# AT88SC12816C.net
KiCad netlist of a schematic drawn in EAGLE
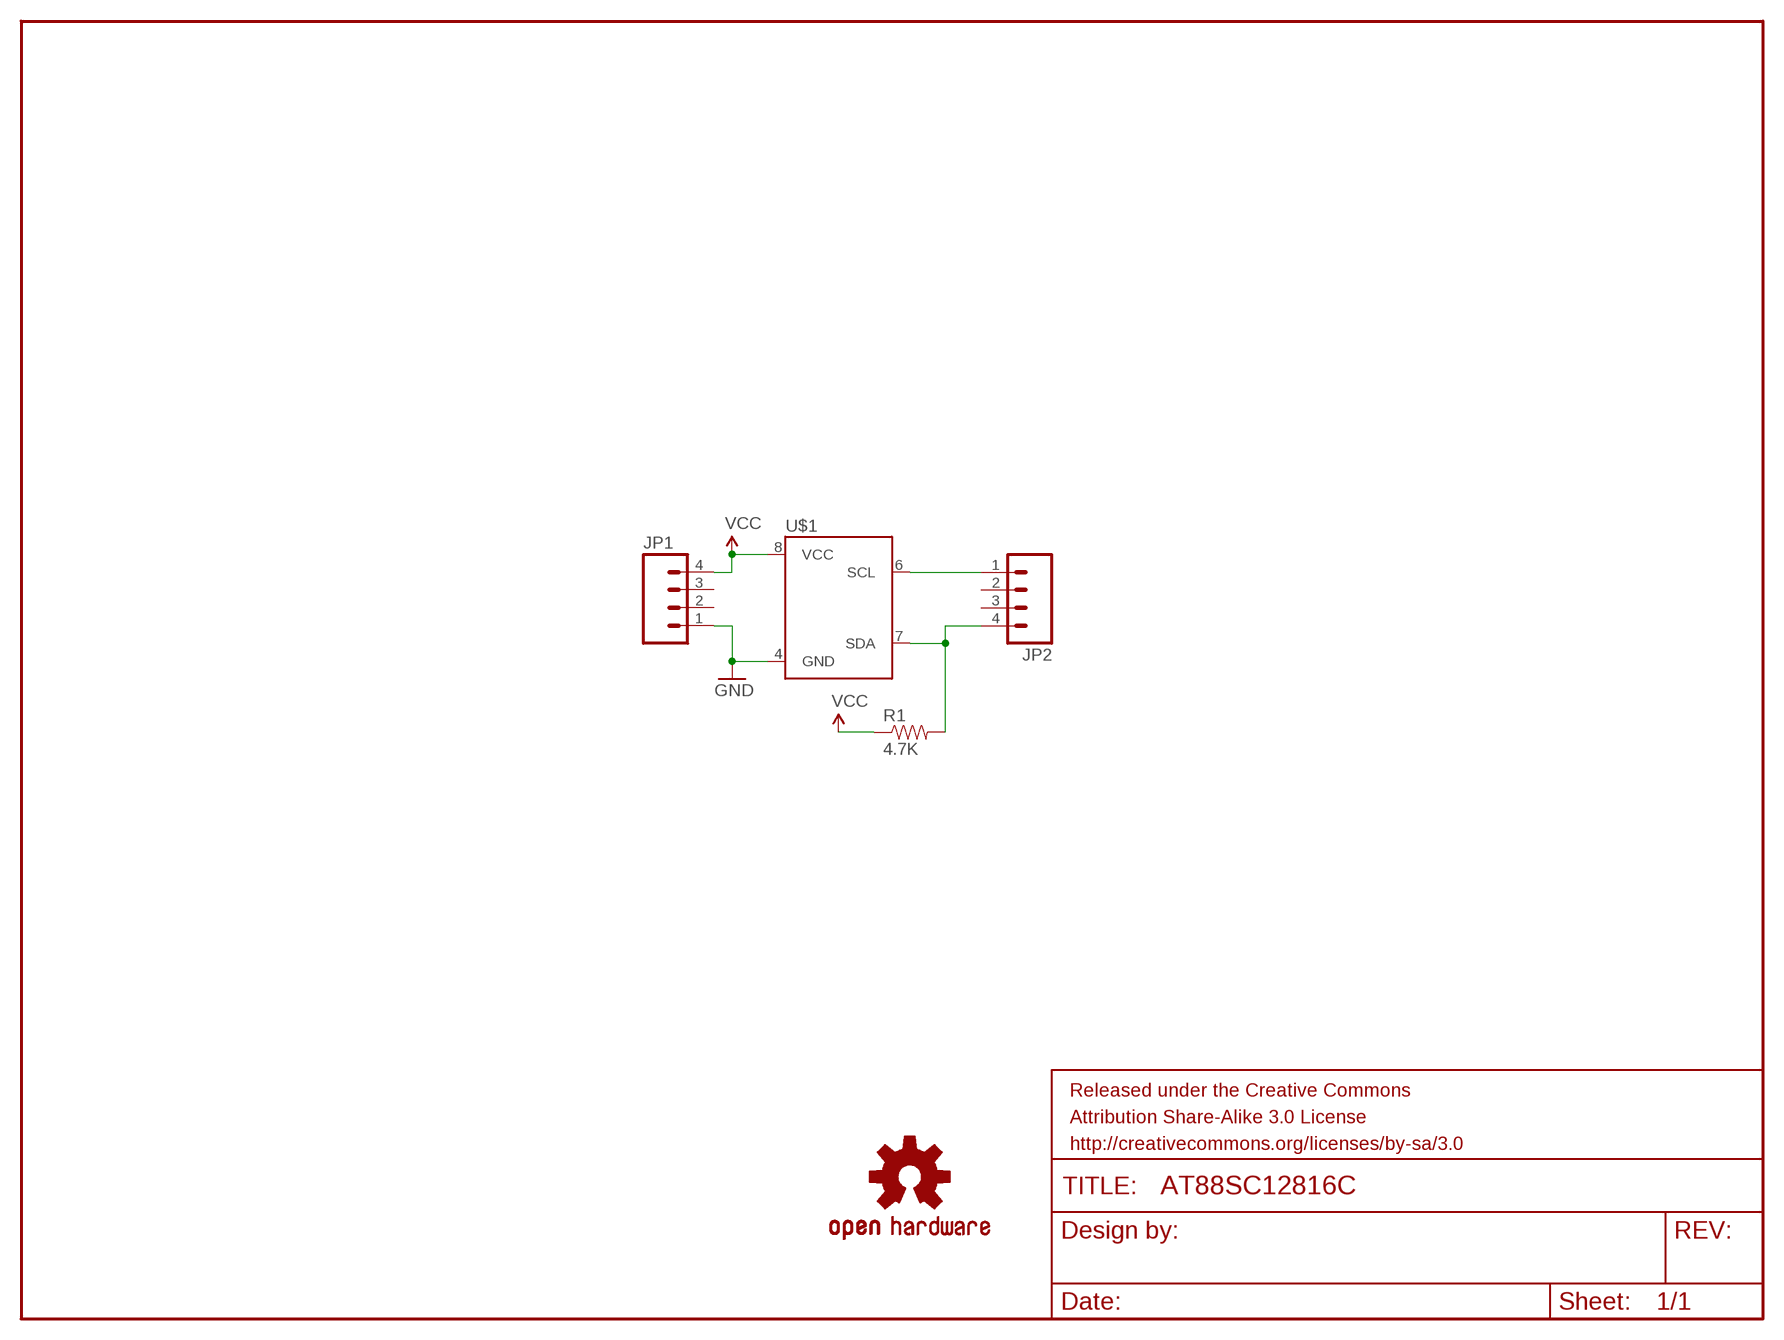
[diagram p0: schematic, sheet 1]

(export (version "E")
  (design (tool "Eeschema 10.0.6"))
  (components
    (comp (ref "FRAME1")
      (value "FRAME-LETTER")
      (footprint "eagle-import:CREATIVE_COMMONS")
      (libsource (lib "eagle-import") (part "FRAME-LETTER"))
    )
    (comp (ref "JP1")
      (value "M04LOCK")
      (footprint "eagle-import:1X04_LOCK")
      (libsource (lib "eagle-import") (part "M04LOCK"))
    )
    (comp (ref "JP2")
      (value "M04LOCK")
      (footprint "eagle-import:1X04_LOCK")
      (libsource (lib "eagle-import") (part "M04LOCK"))
    )
    (comp (ref "LOGO1")
      (value "OSHW-LOGOM")
      (footprint "eagle-import:OSHW-LOGO-M")
      (libsource (lib "eagle-import") (part "OSHW-LOGOM"))
    )
    (comp (ref "R1")
      (value "4.7K")
      (footprint "eagle-import:AXIAL-0.4")
      (libsource (lib "eagle-import") (part "RESISTORPTH-1/4W"))
    )
    (comp (ref "U$1")
      (value "AT88SCAT88SC-PDIP")
      (footprint "eagle-import:DIL08")
      (libsource (lib "eagle-import") (part "AT88SCAT88SC-PDIP"))
    )
  )
  (nets
    (net (code "1") (name "GND") (class "Default")
      (node (ref "JP1") (pin "1") (pinfunction "1_1") (pintype "passive"))
      (node (ref "U$1") (pin "4") (pinfunction "GND_4") (pintype "power_in"))
    )
    (net (code "2") (name "Net-(R1-2)") (class "Default")
      (node (ref "JP2") (pin "4") (pinfunction "4_4") (pintype "passive"))
      (node (ref "R1") (pin "P$2") (pinfunction "2_P$2") (pintype "passive"))
      (node (ref "U$1") (pin "7") (pinfunction "SDA_7") (pintype "bidirectional"))
    )
    (net (code "3") (name "Net-(U$1-SCL)") (class "Default")
      (node (ref "JP2") (pin "1") (pinfunction "1_1") (pintype "passive"))
      (node (ref "U$1") (pin "6") (pinfunction "SCL_6") (pintype "bidirectional"))
    )
    (net (code "4") (name "VCC") (class "Default")
      (node (ref "JP1") (pin "4") (pinfunction "4_4") (pintype "passive"))
      (node (ref "R1") (pin "P$1") (pinfunction "1_P$1") (pintype "passive"))
      (node (ref "U$1") (pin "8") (pinfunction "VCC_8") (pintype "power_in"))
    )
    (net (code "5") (name "unconnected-(JP1-Pad2)") (class "Default")
      (node (ref "JP1") (pin "2") (pinfunction "2_2") (pintype "passive"))
    )
    (net (code "6") (name "unconnected-(JP1-Pad3)") (class "Default")
      (node (ref "JP1") (pin "3") (pinfunction "3_3") (pintype "passive"))
    )
    (net (code "7") (name "unconnected-(JP2-Pad2)") (class "Default")
      (node (ref "JP2") (pin "2") (pinfunction "2_2") (pintype "passive"))
    )
    (net (code "8") (name "unconnected-(JP2-Pad3)") (class "Default")
      (node (ref "JP2") (pin "3") (pinfunction "3_3") (pintype "passive"))
    )
  )
)
